# MCU.net
KiCad netlist of a schematic drawn in Altium Designer
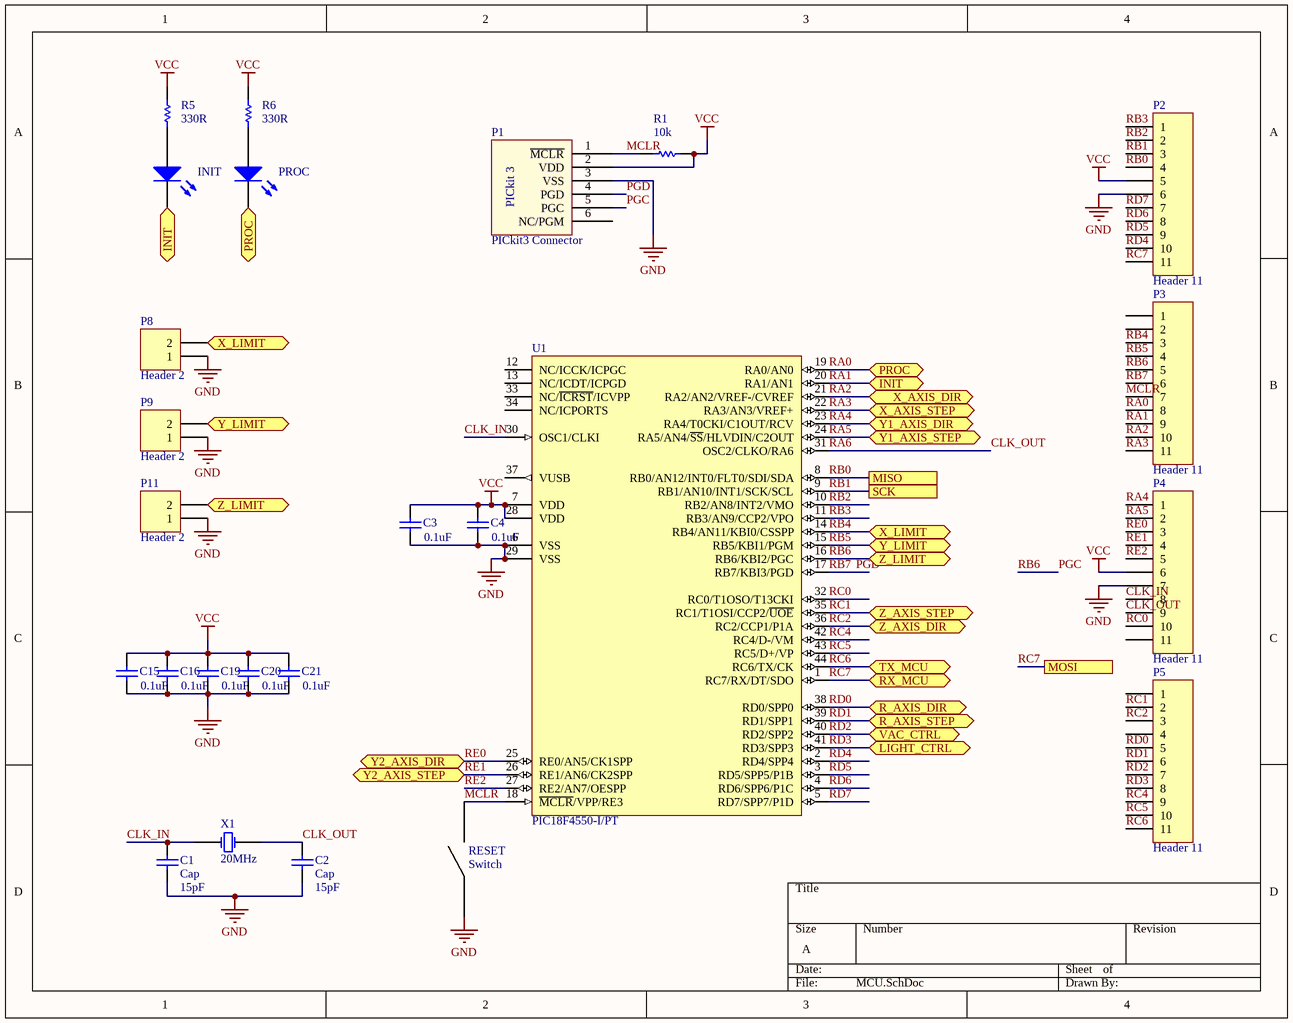
[diagram p0: MCU.SchDoc]

(export (version "E")
  (design (tool "Eeschema 10.0.6"))
  (components
    (comp (ref "C1")
      (value "Cap")
      (footprint "0603")
      (description "Capacitor")
      (fields (field (name "ALTIUM_VALUE") "15pF") (field (name "PUBLISHER") "Altium Limited"))
      (libsource (lib "Miscellaneous Devices") (part "Cap"))
    )
    (comp (ref "C2")
      (value "Cap")
      (footprint "0603")
      (description "Capacitor")
      (fields (field (name "ALTIUM_VALUE") "15pF") (field (name "PUBLISHER") "Altium Limited"))
      (libsource (lib "Miscellaneous Devices") (part "Cap"))
    )
    (comp (ref "C3")
      (value "0.1uF")
      (footprint "0805")
      (description "Capacitor")
      (fields (field (name "Comment") "Cap") (field (name "PUBLISHER") "Altium Limited"))
      (libsource (lib "Miscellaneous Devices") (part "Cap"))
    )
    (comp (ref "C4")
      (value "0.1uF")
      (footprint "0805")
      (description "Capacitor")
      (fields (field (name "Comment") "Cap") (field (name "PUBLISHER") "Altium Limited"))
      (libsource (lib "Miscellaneous Devices") (part "Cap"))
    )
    (comp (ref "C15")
      (value "0.1uF")
      (footprint "0805")
      (description "Capacitor")
      (fields (field (name "Comment") "Cap") (field (name "PUBLISHER") "Altium Limited"))
      (libsource (lib "Miscellaneous Devices") (part "Cap"))
    )
    (comp (ref "C16")
      (value "0.1uF")
      (footprint "0805")
      (description "Capacitor")
      (fields (field (name "Comment") "Cap") (field (name "PUBLISHER") "Altium Limited"))
      (libsource (lib "Miscellaneous Devices") (part "Cap"))
    )
    (comp (ref "C19")
      (value "0.1uF")
      (footprint "0805")
      (description "Capacitor")
      (fields (field (name "Comment") "Cap") (field (name "PUBLISHER") "Altium Limited"))
      (libsource (lib "Miscellaneous Devices") (part "Cap"))
    )
    (comp (ref "C20")
      (value "0.1uF")
      (footprint "0805")
      (description "Capacitor")
      (fields (field (name "Comment") "Cap") (field (name "PUBLISHER") "Altium Limited"))
      (libsource (lib "Miscellaneous Devices") (part "Cap"))
    )
    (comp (ref "C21")
      (value "0.1uF")
      (footprint "0805")
      (description "Capacitor")
      (fields (field (name "Comment") "Cap") (field (name "PUBLISHER") "Altium Limited"))
      (libsource (lib "Miscellaneous Devices") (part "Cap"))
    )
    (comp (ref "INIT")
      (value "LED1")
      (footprint "0805")
      (description "Typical INFRARED GaAs LED")
      (fields (field (name "PUBLISHER") "Altium Limited"))
      (libsource (lib "Miscellaneous Devices") (part "LED0"))
    )
    (comp (ref "P1")
      (value "PICkit3 Connector")
      (footprint "Right Angle PICkit Connector")
      (description "PICkit 3 Connector")
      (libsource (lib "Microcontroller-Related") (part "PICkit 3 Connector"))
    )
    (comp (ref "P2")
      (value "Header 11")
      (footprint "HDR1X11")
      (description "Header, 11-Pin")
      (fields (field (name "PUBLISHER") "Altium Limited"))
      (libsource (lib "Miscellaneous Connectors") (part "Header 11"))
    )
    (comp (ref "P3")
      (value "Header 11")
      (footprint "HDR1X11")
      (description "Header, 11-Pin")
      (fields (field (name "PUBLISHER") "Altium Limited"))
      (libsource (lib "Miscellaneous Connectors") (part "Header 11"))
    )
    (comp (ref "P4")
      (value "Header 11")
      (footprint "HDR1X11")
      (description "Header, 11-Pin")
      (fields (field (name "PUBLISHER") "Altium Limited"))
      (libsource (lib "Miscellaneous Connectors") (part "Header 11"))
    )
    (comp (ref "P5")
      (value "Header 11")
      (footprint "HDR1X11")
      (description "Header, 11-Pin")
      (fields (field (name "PUBLISHER") "Altium Limited"))
      (libsource (lib "Miscellaneous Connectors") (part "Header 11"))
    )
    (comp (ref "P8")
      (value "Header 2")
      (footprint "HDR1X2")
      (description "Header, 2-Pin")
      (fields (field (name "PUBLISHER") "Altium Limited"))
      (libsource (lib "Miscellaneous Connectors") (part "Header 2"))
    )
    (comp (ref "P9")
      (value "Header 2")
      (footprint "HDR1X2")
      (description "Header, 2-Pin")
      (fields (field (name "PUBLISHER") "Altium Limited"))
      (libsource (lib "Miscellaneous Connectors") (part "Header 2"))
    )
    (comp (ref "P11")
      (value "Header 2")
      (footprint "HDR1X2")
      (description "Header, 2-Pin")
      (fields (field (name "PUBLISHER") "Altium Limited"))
      (libsource (lib "Miscellaneous Connectors") (part "Header 2"))
    )
    (comp (ref "PROC")
      (value "LED2")
      (footprint "0805")
      (description "Typical INFRARED GaAs LED")
      (fields (field (name "PUBLISHER") "Altium Limited"))
      (libsource (lib "Miscellaneous Devices") (part "LED0"))
    )
    (comp (ref "R1")
      (value "10k")
      (footprint "0805")
      (description "Resistor")
      (fields (field (name "Comment") "Res1") (field (name "PUBLISHER") "Altium Limited"))
      (libsource (lib "Miscellaneous Devices") (part "Res1"))
    )
    (comp (ref "R5")
      (value "330R")
      (footprint "6-0805_N")
      (description "Resistor")
      (fields (field (name "Comment") "Res1") (field (name "PUBLISHER") "Altium Limited"))
      (libsource (lib "Miscellaneous Devices") (part "Res1"))
    )
    (comp (ref "R6")
      (value "330R")
      (footprint "6-0805_N")
      (description "Resistor")
      (fields (field (name "Comment") "Res1") (field (name "PUBLISHER") "Altium Limited"))
      (libsource (lib "Miscellaneous Devices") (part "Res1"))
    )
    (comp (ref "RESET")
      (value "Switch")
      (footprint "TACT_SWITCH")
      (fields
        (field (name "DIGI-KEY PART NO.") "CKN9112CT-ND")
        (field (name "MANUFACTURER PART NO.") "PTS645SM43SMTR92 LFS")
      )
      (libsource (lib "Electromechanical") (part "Switch"))
    )
    (comp (ref "U1")
      (value "PIC18F4550-I/PT")
      (footprint "TQFP-PT44_N")
      (fields (field (name "PUBLISHER") "Altium Limited"))
      (libsource (lib "Microchip Microcontroller 8-Bit PIC18") (part "PIC18F4550-I/PT"))
    )
    (comp (ref "X1")
      (value "Crystal")
      (footprint "HC49-US")
      (description "2-pin crystal resonator")
      (fields (field (name "FREQUENCY") "20MHz"))
      (libsource (lib "Crystals") (part "Crystal 2-pin"))
    )
  )
  (nets
    (net (code "1") (name "/CLK_IN") (class "Default")
      (node (ref "C1") (pin "2") (pinfunction "2_2") (pintype "passive"))
      (node (ref "P4") (pin "8") (pinfunction "8_8") (pintype "passive"))
      (node (ref "U1") (pin "30") (pinfunction "OSC1/CLKI_30") (pintype "input"))
      (node (ref "X1") (pin "1") (pinfunction "OSC1_1") (pintype "passive"))
    )
    (net (code "2") (name "/CLK_OUT") (class "Default")
      (node (ref "C2") (pin "2") (pinfunction "2_2") (pintype "passive"))
      (node (ref "P4") (pin "9") (pinfunction "9_9") (pintype "passive"))
      (node (ref "U1") (pin "31") (pinfunction "OSC2/CLKO/RA6_31") (pintype "bidirectional"))
      (node (ref "X1") (pin "2") (pinfunction "OSC2_2") (pintype "passive"))
    )
    (net (code "3") (name "/MCLR") (class "Default")
      (node (ref "P1") (pin "1") (pinfunction "~{MCLR}_1") (pintype "passive"))
      (node (ref "P3") (pin "7") (pinfunction "7_7") (pintype "passive"))
      (node (ref "R1") (pin "1") (pinfunction "1_1") (pintype "passive"))
      (node (ref "RESET") (pin "3") (pinfunction "3_3") (pintype "passive"))
      (node (ref "U1") (pin "18") (pinfunction "~{MCLR}/VPP/RE3_18") (pintype "input"))
    )
    (net (code "4") (name "/PGC") (class "Default")
      (node (ref "P1") (pin "5") (pinfunction "PGC_5") (pintype "passive"))
      (node (ref "P11") (pin "2") (pinfunction "2_2") (pintype "passive"))
      (node (ref "P3") (pin "5") (pinfunction "5_5") (pintype "passive"))
      (node (ref "U1") (pin "16") (pinfunction "RB6/KBI2/PGC_16") (pintype "bidirectional"))
    )
    (net (code "5") (name "/PGD") (class "Default")
      (node (ref "P1") (pin "4") (pinfunction "PGD_4") (pintype "passive"))
      (node (ref "P3") (pin "6") (pinfunction "6_6") (pintype "passive"))
      (node (ref "U1") (pin "17") (pinfunction "RB7/KBI3/PGD_17") (pintype "bidirectional"))
    )
    (net (code "6") (name "/RA0") (class "Default")
      (node (ref "P3") (pin "8") (pinfunction "8_8") (pintype "passive"))
      (node (ref "PROC") (pin "2") (pinfunction "K_2") (pintype "passive"))
      (node (ref "U1") (pin "19") (pinfunction "RA0/AN0_19") (pintype "bidirectional"))
    )
    (net (code "7") (name "/RA1") (class "Default")
      (node (ref "INIT") (pin "2") (pinfunction "K_2") (pintype "passive"))
      (node (ref "P3") (pin "9") (pinfunction "9_9") (pintype "passive"))
      (node (ref "U1") (pin "20") (pinfunction "RA1/AN1_20") (pintype "bidirectional"))
    )
    (net (code "8") (name "/RA2") (class "Default")
      (node (ref "P3") (pin "10") (pinfunction "10_10") (pintype "passive"))
      (node (ref "U1") (pin "21") (pinfunction "RA2/AN2/VREF-/CVREF_21") (pintype "bidirectional"))
    )
    (net (code "9") (name "/RA3") (class "Default")
      (node (ref "P3") (pin "11") (pinfunction "11_11") (pintype "passive"))
      (node (ref "U1") (pin "22") (pinfunction "RA3/AN3/VREF+_22") (pintype "bidirectional"))
    )
    (net (code "10") (name "/RA4") (class "Default")
      (node (ref "P4") (pin "1") (pinfunction "1_1") (pintype "passive"))
      (node (ref "U1") (pin "23") (pinfunction "RA4/T0CKI/C1OUT/RCV_23") (pintype "bidirectional"))
    )
    (net (code "11") (name "/RA5") (class "Default")
      (node (ref "P4") (pin "2") (pinfunction "2_2") (pintype "passive"))
      (node (ref "U1") (pin "24") (pinfunction "RA5/AN4/~{SS}/HLVDIN/C2OUT_24") (pintype "bidirectional"))
    )
    (net (code "12") (name "/RB0") (class "Default")
      (node (ref "P2") (pin "4") (pinfunction "4_4") (pintype "passive"))
      (node (ref "U1") (pin "8") (pinfunction "RB0/AN12/INT0/FLT0/SDI/SDA_8") (pintype "bidirectional"))
    )
    (net (code "13") (name "/RB1") (class "Default")
      (node (ref "P2") (pin "3") (pinfunction "3_3") (pintype "passive"))
      (node (ref "U1") (pin "9") (pinfunction "RB1/AN10/INT1/SCK/SCL_9") (pintype "bidirectional"))
    )
    (net (code "14") (name "/RB2") (class "Default")
      (node (ref "P2") (pin "2") (pinfunction "2_2") (pintype "passive"))
      (node (ref "U1") (pin "10") (pinfunction "RB2/AN8/INT2/VMO_10") (pintype "bidirectional"))
    )
    (net (code "15") (name "/RB3") (class "Default")
      (node (ref "P2") (pin "1") (pinfunction "1_1") (pintype "passive"))
      (node (ref "U1") (pin "11") (pinfunction "RB3/AN9/CCP2/VPO_11") (pintype "bidirectional"))
    )
    (net (code "16") (name "/RB4") (class "Default")
      (node (ref "P3") (pin "3") (pinfunction "3_3") (pintype "passive"))
      (node (ref "P8") (pin "2") (pinfunction "2_2") (pintype "passive"))
      (node (ref "U1") (pin "14") (pinfunction "RB4/AN11/KBI0/CSSPP_14") (pintype "bidirectional"))
    )
    (net (code "17") (name "/RB5") (class "Default")
      (node (ref "P3") (pin "4") (pinfunction "4_4") (pintype "passive"))
      (node (ref "P9") (pin "2") (pinfunction "2_2") (pintype "passive"))
      (node (ref "U1") (pin "15") (pinfunction "RB5/KBI1/PGM_15") (pintype "bidirectional"))
    )
    (net (code "18") (name "/RC0") (class "Default")
      (node (ref "P4") (pin "10") (pinfunction "10_10") (pintype "passive"))
      (node (ref "U1") (pin "32") (pinfunction "RC0/T1OSO/T13CKI_32") (pintype "bidirectional"))
    )
    (net (code "19") (name "/RC1") (class "Default")
      (node (ref "P5") (pin "2") (pinfunction "2_2") (pintype "passive"))
      (node (ref "U1") (pin "35") (pinfunction "RC1/T1OSI/CCP2/~{UOE}_35") (pintype "bidirectional"))
    )
    (net (code "20") (name "/RC2") (class "Default")
      (node (ref "P5") (pin "3") (pinfunction "3_3") (pintype "passive"))
      (node (ref "U1") (pin "36") (pinfunction "RC2/CCP1/P1A_36") (pintype "bidirectional"))
    )
    (net (code "21") (name "/RC4") (class "Default")
      (node (ref "P5") (pin "9") (pinfunction "9_9") (pintype "passive"))
      (node (ref "U1") (pin "42") (pinfunction "RC4/D-/VM_42") (pintype "bidirectional"))
    )
    (net (code "22") (name "/RC5") (class "Default")
      (node (ref "P5") (pin "10") (pinfunction "10_10") (pintype "passive"))
      (node (ref "U1") (pin "43") (pinfunction "RC5/D+/VP_43") (pintype "bidirectional"))
    )
    (net (code "23") (name "/RC6") (class "Default")
      (node (ref "P5") (pin "11") (pinfunction "11_11") (pintype "passive"))
      (node (ref "U1") (pin "44") (pinfunction "RC6/TX/CK_44") (pintype "bidirectional"))
    )
    (net (code "24") (name "/RC7") (class "Default")
      (node (ref "P2") (pin "11") (pinfunction "11_11") (pintype "passive"))
      (node (ref "U1") (pin "1") (pinfunction "RC7/RX/DT/SDO_1") (pintype "bidirectional"))
    )
    (net (code "25") (name "/RD0") (class "Default")
      (node (ref "P5") (pin "5") (pinfunction "5_5") (pintype "passive"))
      (node (ref "U1") (pin "38") (pinfunction "RD0/SPP0_38") (pintype "bidirectional"))
    )
    (net (code "26") (name "/RD1") (class "Default")
      (node (ref "P5") (pin "6") (pinfunction "6_6") (pintype "passive"))
      (node (ref "U1") (pin "39") (pinfunction "RD1/SPP1_39") (pintype "bidirectional"))
    )
    (net (code "27") (name "/RD2") (class "Default")
      (node (ref "P5") (pin "7") (pinfunction "7_7") (pintype "passive"))
      (node (ref "U1") (pin "40") (pinfunction "RD2/SPP2_40") (pintype "bidirectional"))
    )
    (net (code "28") (name "/RD3") (class "Default")
      (node (ref "P5") (pin "8") (pinfunction "8_8") (pintype "passive"))
      (node (ref "U1") (pin "41") (pinfunction "RD3/SPP3_41") (pintype "bidirectional"))
    )
    (net (code "29") (name "/RD4") (class "Default")
      (node (ref "P2") (pin "10") (pinfunction "10_10") (pintype "passive"))
      (node (ref "U1") (pin "2") (pinfunction "RD4/SPP4_2") (pintype "bidirectional"))
    )
    (net (code "30") (name "/RD5") (class "Default")
      (node (ref "P2") (pin "9") (pinfunction "9_9") (pintype "passive"))
      (node (ref "U1") (pin "3") (pinfunction "RD5/SPP5/P1B_3") (pintype "bidirectional"))
    )
    (net (code "31") (name "/RD6") (class "Default")
      (node (ref "P2") (pin "8") (pinfunction "8_8") (pintype "passive"))
      (node (ref "U1") (pin "4") (pinfunction "RD6/SPP6/P1C_4") (pintype "bidirectional"))
    )
    (net (code "32") (name "/RD7") (class "Default")
      (node (ref "P2") (pin "7") (pinfunction "7_7") (pintype "passive"))
      (node (ref "U1") (pin "5") (pinfunction "RD7/SPP7/P1D_5") (pintype "bidirectional"))
    )
    (net (code "33") (name "/RE0") (class "Default")
      (node (ref "P4") (pin "3") (pinfunction "3_3") (pintype "passive"))
      (node (ref "U1") (pin "25") (pinfunction "RE0/AN5/CK1SPP_25") (pintype "bidirectional"))
    )
    (net (code "34") (name "/RE1") (class "Default")
      (node (ref "P4") (pin "4") (pinfunction "4_4") (pintype "passive"))
      (node (ref "U1") (pin "26") (pinfunction "RE1/AN6/CK2SPP_26") (pintype "bidirectional"))
    )
    (net (code "35") (name "/RE2") (class "Default")
      (node (ref "P4") (pin "5") (pinfunction "5_5") (pintype "passive"))
      (node (ref "U1") (pin "27") (pinfunction "RE2/AN7/OESPP_27") (pintype "bidirectional"))
    )
    (net (code "36") (name "1") (class "Default")
      (node (ref "RESET") (pin "2") (pinfunction "2_2") (pintype "passive"))
    )
    (net (code "37") (name "4") (class "Default")
      (node (ref "RESET") (pin "4") (pinfunction "4_4") (pintype "passive"))
    )
    (net (code "38") (name "GND") (class "Default")
      (node (ref "C1") (pin "1") (pinfunction "1_1") (pintype "passive"))
      (node (ref "C15") (pin "1") (pinfunction "1_1") (pintype "passive"))
      (node (ref "C16") (pin "1") (pinfunction "1_1") (pintype "passive"))
      (node (ref "C19") (pin "1") (pinfunction "1_1") (pintype "passive"))
      (node (ref "C2") (pin "1") (pinfunction "1_1") (pintype "passive"))
      (node (ref "C20") (pin "1") (pinfunction "1_1") (pintype "passive"))
      (node (ref "C21") (pin "1") (pinfunction "1_1") (pintype "passive"))
      (node (ref "C3") (pin "1") (pinfunction "1_1") (pintype "passive"))
      (node (ref "C4") (pin "1") (pinfunction "1_1") (pintype "passive"))
      (node (ref "P1") (pin "3") (pinfunction "VSS_3") (pintype "passive"))
      (node (ref "P11") (pin "1") (pinfunction "1_1") (pintype "passive"))
      (node (ref "P2") (pin "6") (pinfunction "6_6") (pintype "passive"))
      (node (ref "P4") (pin "7") (pinfunction "7_7") (pintype "passive"))
      (node (ref "P8") (pin "1") (pinfunction "1_1") (pintype "passive"))
      (node (ref "P9") (pin "1") (pinfunction "1_1") (pintype "passive"))
      (node (ref "RESET") (pin "1") (pinfunction "1_1") (pintype "passive"))
      (node (ref "U1") (pin "29") (pinfunction "VSS_29") (pintype "power_in"))
      (node (ref "U1") (pin "6") (pinfunction "VSS_6") (pintype "power_in"))
    )
    (net (code "39") (name "Net-(INIT-A)") (class "Default")
      (node (ref "INIT") (pin "1") (pinfunction "A_1") (pintype "passive"))
      (node (ref "R5") (pin "1") (pinfunction "1_1") (pintype "passive"))
    )
    (net (code "40") (name "Net-(PROC-A)") (class "Default")
      (node (ref "PROC") (pin "1") (pinfunction "A_1") (pintype "passive"))
      (node (ref "R6") (pin "1") (pinfunction "1_1") (pintype "passive"))
    )
    (net (code "41") (name "VCC") (class "Default")
      (node (ref "C15") (pin "2") (pinfunction "2_2") (pintype "passive"))
      (node (ref "C16") (pin "2") (pinfunction "2_2") (pintype "passive"))
      (node (ref "C19") (pin "2") (pinfunction "2_2") (pintype "passive"))
      (node (ref "C20") (pin "2") (pinfunction "2_2") (pintype "passive"))
      (node (ref "C21") (pin "2") (pinfunction "2_2") (pintype "passive"))
      (node (ref "C3") (pin "2") (pinfunction "2_2") (pintype "passive"))
      (node (ref "C4") (pin "2") (pinfunction "2_2") (pintype "passive"))
      (node (ref "P1") (pin "2") (pinfunction "VDD_2") (pintype "passive"))
      (node (ref "P2") (pin "5") (pinfunction "5_5") (pintype "passive"))
      (node (ref "P4") (pin "6") (pinfunction "6_6") (pintype "passive"))
      (node (ref "R1") (pin "2") (pinfunction "2_2") (pintype "passive"))
      (node (ref "R5") (pin "2") (pinfunction "2_2") (pintype "passive"))
      (node (ref "R6") (pin "2") (pinfunction "2_2") (pintype "passive"))
      (node (ref "U1") (pin "28") (pinfunction "VDD_28") (pintype "power_in"))
      (node (ref "U1") (pin "7") (pinfunction "VDD_7") (pintype "power_in"))
    )
    (net (code "42") (name "unconnected-(P1-NC{slash}PGM-Pad6)") (class "Default")
      (node (ref "P1") (pin "6") (pinfunction "NC/PGM_6") (pintype "passive"))
    )
    (net (code "43") (name "unconnected-(P3-Pad1)") (class "Default")
      (node (ref "P3") (pin "1") (pinfunction "1_1") (pintype "passive"))
    )
    (net (code "44") (name "unconnected-(P3-Pad2)") (class "Default")
      (node (ref "P3") (pin "2") (pinfunction "2_2") (pintype "passive"))
    )
    (net (code "45") (name "unconnected-(P4-Pad11)") (class "Default")
      (node (ref "P4") (pin "11") (pinfunction "11_11") (pintype "passive"))
    )
    (net (code "46") (name "unconnected-(P5-Pad1)") (class "Default")
      (node (ref "P5") (pin "1") (pinfunction "1_1") (pintype "passive"))
    )
    (net (code "47") (name "unconnected-(P5-Pad4)") (class "Default")
      (node (ref "P5") (pin "4") (pinfunction "4_4") (pintype "passive"))
    )
    (net (code "48") (name "unconnected-(U1-NC{slash}ICCK{slash}ICPGC-Pad12)") (class "Default")
      (node (ref "U1") (pin "12") (pinfunction "NC/ICCK/ICPGC_12") (pintype "passive"))
    )
    (net (code "49") (name "unconnected-(U1-NC{slash}ICDT{slash}ICPGD-Pad13)") (class "Default")
      (node (ref "U1") (pin "13") (pinfunction "NC/ICDT/ICPGD_13") (pintype "passive"))
    )
    (net (code "50") (name "unconnected-(U1-NC{slash}ICPORTS-Pad34)") (class "Default")
      (node (ref "U1") (pin "34") (pinfunction "NC/ICPORTS_34") (pintype "passive"))
    )
    (net (code "51") (name "unconnected-(U1-NC{slash}~{ICRST}{slash}ICVPP-Pad33)") (class "Default")
      (node (ref "U1") (pin "33") (pinfunction "NC/~{ICRST}/ICVPP_33") (pintype "passive"))
    )
    (net (code "52") (name "unconnected-(U1-VUSB-Pad37)") (class "Default")
      (node (ref "U1") (pin "37") (pinfunction "VUSB_37") (pintype "output"))
    )
  )
)
